# interfaceUART_I2C.net
KiCad netlist of a schematic drawn in Altium Designer
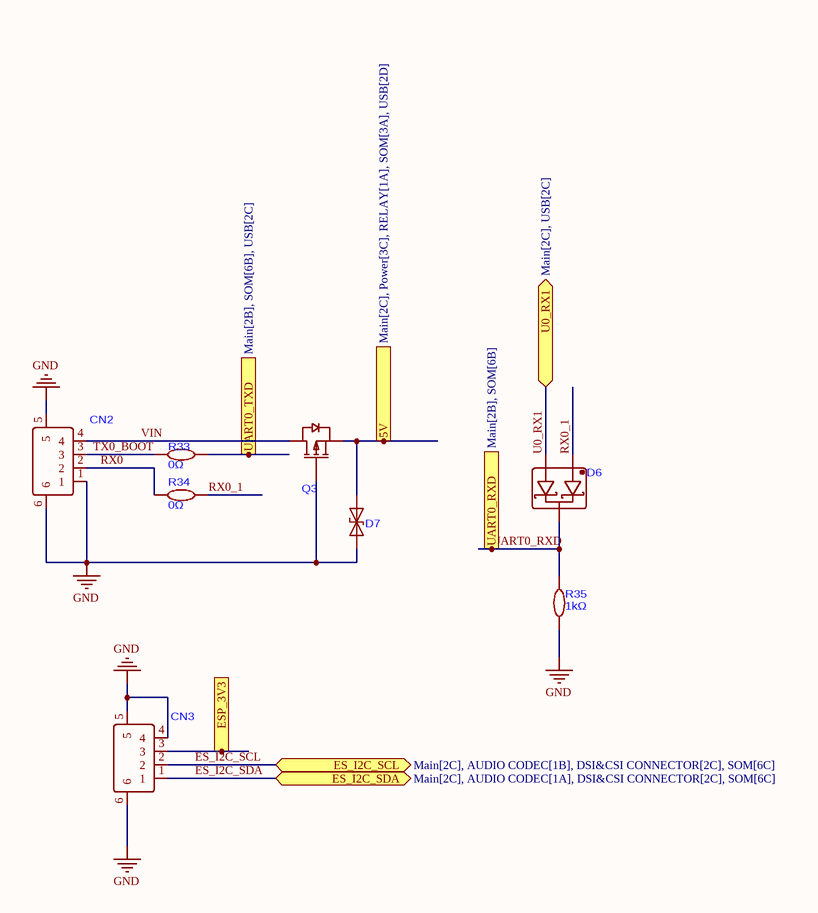
[diagram p0: interfaceUART&I2C.SchDoc]

(export (version "E")
  (design (tool "Eeschema 10.0.6"))
  (components
    (comp (ref "CN2")
      (value "533980471")
      (footprint "CONN-SMD_4P-P1.25_XUNPU_WAFER-GH1.25-4PWB")
      (libsource (lib "Schlib2") (part "533980471"))
    )
    (comp (ref "CN3")
      (value "533980471")
      (footprint "CONN-SMD_4P-P1.25_XUNPU_WAFER-GH1.25-4PWB")
      (libsource (lib "Schlib2") (part "533980471"))
    )
    (comp (ref "D6")
      (value "DIODE ARR SCHOTTKY 30V SOT-23")
      (footprint "SOT-23-3_L2.9-W1.3-P1.90-LS2.4-BR")
      (description "600mA 30V 1 Pair Common Cathode 1V@100mA 200mA SOT-23 Single Diodes RoHS")
      (libsource (lib "Schlib2") (part "BAT54C_C916424"))
    )
    (comp (ref "D7")
      (value "TVS DIODE 5VWM 9.2VC DO-214AA")
      (footprint "SMB_L4.6-W3.6-LS5.3-BI")
      (description "65.3A 600W 9.2V 6.4V Bidirectional 5V DO-214AA TVS Diodes RoHS")
      (libsource (lib "Schlib2") (part "SMBJ5.0CA_C83323"))
    )
    (comp (ref "Q3")
      (value "MOSFET P-CH 30V 4.3A SOT-23")
      (footprint "SOT-23-3_L2.9-W1.6-P1.90-LS2.8-BR")
      (description "30V 4.3A 48mΩ@10V 2.5V@250uA 1 P-Channel SOT-23 Single FETs, MOSFETs ROHS")
      (libsource (lib "Schlib2") (part "AO3407A"))
    )
    (comp (ref "R33")
      (value "0Ω")
      (footprint "R0603")
      (description "100mW 0Ω 75V Thick Film Resistor ±5% 0603 Chip Resistor - Surface Mount RoHS")
      (libsource (lib "Schlib2") (part "RC0603JR-070RL"))
    )
    (comp (ref "R34")
      (value "0Ω")
      (footprint "R0603")
      (description "100mW 0Ω 75V Thick Film Resistor ±5% 0603 Chip Resistor - Surface Mount RoHS")
      (libsource (lib "Schlib2") (part "RC0603JR-070RL"))
    )
    (comp (ref "R35")
      (value "1kΩ")
      (footprint "R0603")
      (description "100mW 1kΩ 50V ±100ppm/℃ Thick Film Resistor ±5% 0603 Chip Resistor - Surface Mount ROHS")
      (libsource (lib "Schlib2") (part "RMC 0603 1K J N"))
    )
  )
  (nets
    (net (code "1") (name "/5V") (class "Default")
      (node (ref "D7") (pin "2") (pinfunction "A_2") (pintype "passive"))
      (node (ref "Q3") (pin "2") (pinfunction "S_2") (pintype "passive"))
    )
    (net (code "2") (name "/ESP_3V3") (class "Default")
      (node (ref "CN3") (pin "3") (pinfunction "3_3") (pintype "passive"))
    )
    (net (code "3") (name "/ES_I2C_SCL") (class "Default")
      (node (ref "CN3") (pin "2") (pinfunction "2_2") (pintype "passive"))
    )
    (net (code "4") (name "/ES_I2C_SDA") (class "Default")
      (node (ref "CN3") (pin "1") (pinfunction "1_1") (pintype "passive"))
    )
    (net (code "5") (name "/RX0") (class "Default")
      (node (ref "CN2") (pin "2") (pinfunction "2_2") (pintype "passive"))
      (node (ref "R34") (pin "1") (pinfunction "1_1") (pintype "passive"))
    )
    (net (code "6") (name "/RX0_1") (class "Default")
      (node (ref "D6") (pin "1") (pinfunction "1_1") (pintype "passive"))
      (node (ref "R34") (pin "2") (pinfunction "2_2") (pintype "passive"))
    )
    (net (code "7") (name "/TX0_BOOT") (class "Default")
      (node (ref "CN2") (pin "3") (pinfunction "3_3") (pintype "passive"))
      (node (ref "R33") (pin "1") (pinfunction "1_1") (pintype "passive"))
    )
    (net (code "8") (name "/U0_RX1") (class "Default")
      (node (ref "D6") (pin "2") (pinfunction "2_2") (pintype "passive"))
    )
    (net (code "9") (name "/UART0_RXD") (class "Default")
      (node (ref "D6") (pin "3") (pinfunction "3_3") (pintype "passive"))
      (node (ref "R35") (pin "2") (pinfunction "2_2") (pintype "passive"))
    )
    (net (code "10") (name "/UART0_TXD") (class "Default")
      (node (ref "R33") (pin "2") (pinfunction "2_2") (pintype "passive"))
    )
    (net (code "11") (name "/VIN") (class "Default")
      (node (ref "CN2") (pin "4") (pinfunction "4_4") (pintype "passive"))
      (node (ref "Q3") (pin "3") (pinfunction "D_3") (pintype "passive"))
    )
    (net (code "12") (name "GND") (class "Default")
      (node (ref "CN2") (pin "1") (pinfunction "1_1") (pintype "passive"))
      (node (ref "CN2") (pin "5") (pinfunction "5_5") (pintype "passive"))
      (node (ref "CN2") (pin "6") (pinfunction "6_6") (pintype "passive"))
      (node (ref "CN3") (pin "4") (pinfunction "4_4") (pintype "passive"))
      (node (ref "CN3") (pin "5") (pinfunction "5_5") (pintype "passive"))
      (node (ref "CN3") (pin "6") (pinfunction "6_6") (pintype "passive"))
      (node (ref "D7") (pin "1") (pinfunction "K_1") (pintype "passive"))
      (node (ref "Q3") (pin "1") (pinfunction "G_1") (pintype "passive"))
      (node (ref "R35") (pin "1") (pinfunction "1_1") (pintype "passive"))
    )
  )
)
